# Science_Fair_Project.net
KiCad netlist of a schematic drawn in EAGLE
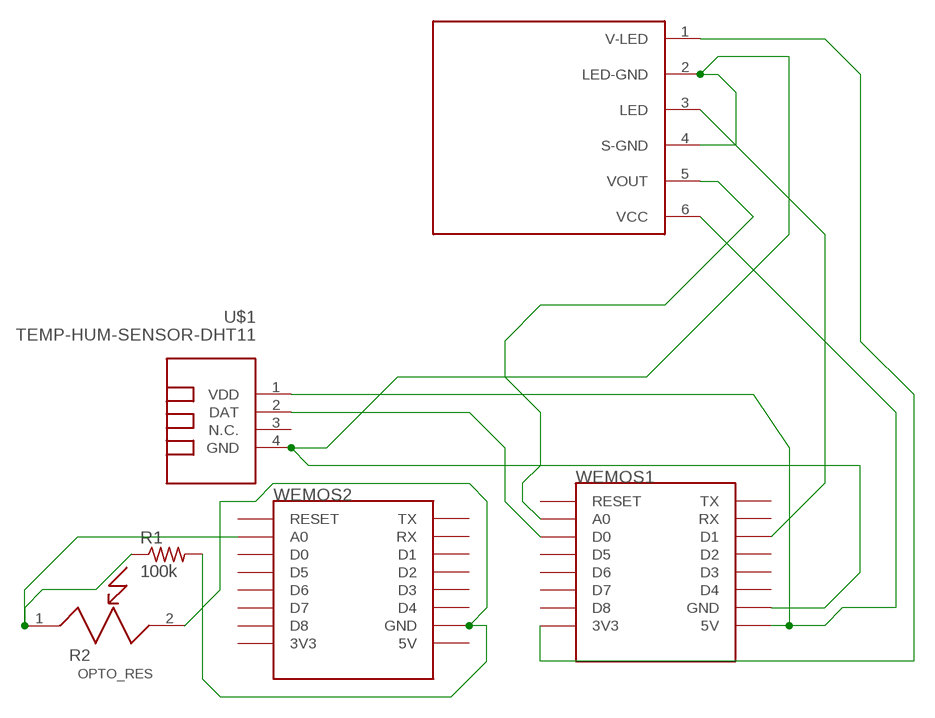
[diagram p0: schematic, sheet 1]

(export (version "E")
  (design (tool "Eeschema 10.0.6"))
  (components
    (comp (ref "R1")
      (value "100k")
      (footprint "eagle-import:0411_15")
      (libsource (lib "eagle-import") (part "R-US_0411/15"))
    )
    (comp (ref "R2")
      (value "OPTO_RES")
      (footprint "eagle-import:OPTO_RES")
      (libsource (lib "eagle-import") (part "OPTO_RES"))
    )
    (comp (ref "U$1")
      (value "TEMP-HUM-SENSOR-DHT11")
      (footprint "eagle-import:TEMP-HUM-SENSOR-DHT11")
      (libsource (lib "eagle-import") (part "TEMP-HUM-SENSOR-DHT11"))
    )
    (comp (ref "U$2")
      (value "GP2Y1010AU")
      (footprint "eagle-import:GP2Y1010AU")
      (libsource (lib "eagle-import") (part "GP2Y1010AU"))
    )
    (comp (ref "WEMOS1")
      (value "WEMOS-D1-MINI")
      (footprint "eagle-import:WEMOS-D1-MINI")
      (libsource (lib "eagle-import") (part "WEMOS-D1-MINI"))
    )
    (comp (ref "WEMOS2")
      (value "WEMOS-D1-MINI")
      (footprint "eagle-import:WEMOS-D1-MINI")
      (libsource (lib "eagle-import") (part "WEMOS-D1-MINI"))
    )
  )
  (nets
    (net (code "1") (name "Net-(R2-P1)") (class "Default")
      (node (ref "R1") (pin "1") (pinfunction "1_1") (pintype "passive"))
      (node (ref "R2") (pin "1") (pinfunction "P1_1") (pintype "bidirectional"))
      (node (ref "WEMOS2") (pin "A0") (pinfunction "A0_A0") (pintype "bidirectional"))
    )
    (net (code "2") (name "Net-(R2-P2)") (class "Default")
      (node (ref "R1") (pin "2") (pinfunction "2_2") (pintype "passive"))
      (node (ref "R2") (pin "2") (pinfunction "P2_2") (pintype "bidirectional"))
      (node (ref "WEMOS2") (pin "GND") (pinfunction "GND_GND") (pintype "bidirectional"))
    )
    (net (code "3") (name "Net-(U$1-DAT)") (class "Default")
      (node (ref "U$1") (pin "2") (pinfunction "DAT_2") (pintype "bidirectional"))
      (node (ref "WEMOS1") (pin "D0") (pinfunction "D0_D0") (pintype "bidirectional"))
    )
    (net (code "4") (name "Net-(U$1-GND)") (class "Default")
      (node (ref "U$1") (pin "4") (pinfunction "GND_4") (pintype "power_in"))
      (node (ref "U$2") (pin "2") (pinfunction "LED-GND_2") (pintype "power_in"))
      (node (ref "U$2") (pin "4") (pinfunction "S-GND_4") (pintype "power_in"))
      (node (ref "WEMOS1") (pin "GND") (pinfunction "GND_GND") (pintype "bidirectional"))
    )
    (net (code "5") (name "Net-(U$1-VDD)") (class "Default")
      (node (ref "U$1") (pin "1") (pinfunction "VDD_1") (pintype "power_in"))
      (node (ref "U$2") (pin "6") (pinfunction "VCC_6") (pintype "power_in"))
      (node (ref "WEMOS1") (pin "5V") (pinfunction "5V_5V") (pintype "bidirectional"))
    )
    (net (code "6") (name "Net-(U$2-LED)") (class "Default")
      (node (ref "U$2") (pin "3") (pinfunction "LED_3") (pintype "input"))
      (node (ref "WEMOS1") (pin "D1") (pinfunction "D1_D1") (pintype "bidirectional"))
    )
    (net (code "7") (name "Net-(U$2-V-LED)") (class "Default")
      (node (ref "U$2") (pin "1") (pinfunction "V-LED_1") (pintype "power_in"))
      (node (ref "WEMOS1") (pin "3V3") (pinfunction "3V3_3V3") (pintype "bidirectional"))
    )
    (net (code "8") (name "Net-(U$2-VOUT)") (class "Default")
      (node (ref "U$2") (pin "5") (pinfunction "VOUT_5") (pintype "output"))
      (node (ref "WEMOS1") (pin "A0") (pinfunction "A0_A0") (pintype "bidirectional"))
    )
    (net (code "9") (name "unconnected-(U$1-N.C.-Pad3)") (class "Default")
      (node (ref "U$1") (pin "3") (pinfunction "N.C._3") (pintype "passive"))
    )
    (net (code "10") (name "unconnected-(WEMOS1-PadD2)") (class "Default")
      (node (ref "WEMOS1") (pin "D2") (pinfunction "D2_D2") (pintype "bidirectional"))
    )
    (net (code "11") (name "unconnected-(WEMOS1-PadD3)") (class "Default")
      (node (ref "WEMOS1") (pin "D3") (pinfunction "D3_D3") (pintype "bidirectional"))
    )
    (net (code "12") (name "unconnected-(WEMOS1-PadD4)") (class "Default")
      (node (ref "WEMOS1") (pin "D4") (pinfunction "D4_D4") (pintype "bidirectional"))
    )
    (net (code "13") (name "unconnected-(WEMOS1-PadD5)") (class "Default")
      (node (ref "WEMOS1") (pin "D5") (pinfunction "D5_D5") (pintype "bidirectional"))
    )
    (net (code "14") (name "unconnected-(WEMOS1-PadD6)") (class "Default")
      (node (ref "WEMOS1") (pin "D6") (pinfunction "D6_D6") (pintype "bidirectional"))
    )
    (net (code "15") (name "unconnected-(WEMOS1-PadD7)") (class "Default")
      (node (ref "WEMOS1") (pin "D7") (pinfunction "D7_D7") (pintype "bidirectional"))
    )
    (net (code "16") (name "unconnected-(WEMOS1-PadD8)") (class "Default")
      (node (ref "WEMOS1") (pin "D8") (pinfunction "D8_D8") (pintype "bidirectional"))
    )
    (net (code "17") (name "unconnected-(WEMOS1-PadRESET)") (class "Default")
      (node (ref "WEMOS1") (pin "RESET") (pinfunction "RESET_RESET") (pintype "bidirectional"))
    )
    (net (code "18") (name "unconnected-(WEMOS1-PadRX)") (class "Default")
      (node (ref "WEMOS1") (pin "RX") (pinfunction "RX_RX") (pintype "bidirectional"))
    )
    (net (code "19") (name "unconnected-(WEMOS1-PadTX)") (class "Default")
      (node (ref "WEMOS1") (pin "TX") (pinfunction "TX_TX") (pintype "bidirectional"))
    )
    (net (code "20") (name "unconnected-(WEMOS2-Pad3V3)") (class "Default")
      (node (ref "WEMOS2") (pin "3V3") (pinfunction "3V3_3V3") (pintype "bidirectional"))
    )
    (net (code "21") (name "unconnected-(WEMOS2-Pad5V)") (class "Default")
      (node (ref "WEMOS2") (pin "5V") (pinfunction "5V_5V") (pintype "bidirectional"))
    )
    (net (code "22") (name "unconnected-(WEMOS2-PadD0)") (class "Default")
      (node (ref "WEMOS2") (pin "D0") (pinfunction "D0_D0") (pintype "bidirectional"))
    )
    (net (code "23") (name "unconnected-(WEMOS2-PadD1)") (class "Default")
      (node (ref "WEMOS2") (pin "D1") (pinfunction "D1_D1") (pintype "bidirectional"))
    )
    (net (code "24") (name "unconnected-(WEMOS2-PadD2)") (class "Default")
      (node (ref "WEMOS2") (pin "D2") (pinfunction "D2_D2") (pintype "bidirectional"))
    )
    (net (code "25") (name "unconnected-(WEMOS2-PadD3)") (class "Default")
      (node (ref "WEMOS2") (pin "D3") (pinfunction "D3_D3") (pintype "bidirectional"))
    )
    (net (code "26") (name "unconnected-(WEMOS2-PadD4)") (class "Default")
      (node (ref "WEMOS2") (pin "D4") (pinfunction "D4_D4") (pintype "bidirectional"))
    )
    (net (code "27") (name "unconnected-(WEMOS2-PadD5)") (class "Default")
      (node (ref "WEMOS2") (pin "D5") (pinfunction "D5_D5") (pintype "bidirectional"))
    )
    (net (code "28") (name "unconnected-(WEMOS2-PadD6)") (class "Default")
      (node (ref "WEMOS2") (pin "D6") (pinfunction "D6_D6") (pintype "bidirectional"))
    )
    (net (code "29") (name "unconnected-(WEMOS2-PadD7)") (class "Default")
      (node (ref "WEMOS2") (pin "D7") (pinfunction "D7_D7") (pintype "bidirectional"))
    )
    (net (code "30") (name "unconnected-(WEMOS2-PadD8)") (class "Default")
      (node (ref "WEMOS2") (pin "D8") (pinfunction "D8_D8") (pintype "bidirectional"))
    )
    (net (code "31") (name "unconnected-(WEMOS2-PadRESET)") (class "Default")
      (node (ref "WEMOS2") (pin "RESET") (pinfunction "RESET_RESET") (pintype "bidirectional"))
    )
    (net (code "32") (name "unconnected-(WEMOS2-PadRX)") (class "Default")
      (node (ref "WEMOS2") (pin "RX") (pinfunction "RX_RX") (pintype "bidirectional"))
    )
    (net (code "33") (name "unconnected-(WEMOS2-PadTX)") (class "Default")
      (node (ref "WEMOS2") (pin "TX") (pinfunction "TX_TX") (pintype "bidirectional"))
    )
  )
)
